# pocket_scope_test_front_end_v0001.net
KiCad netlist of a schematic drawn in EAGLE
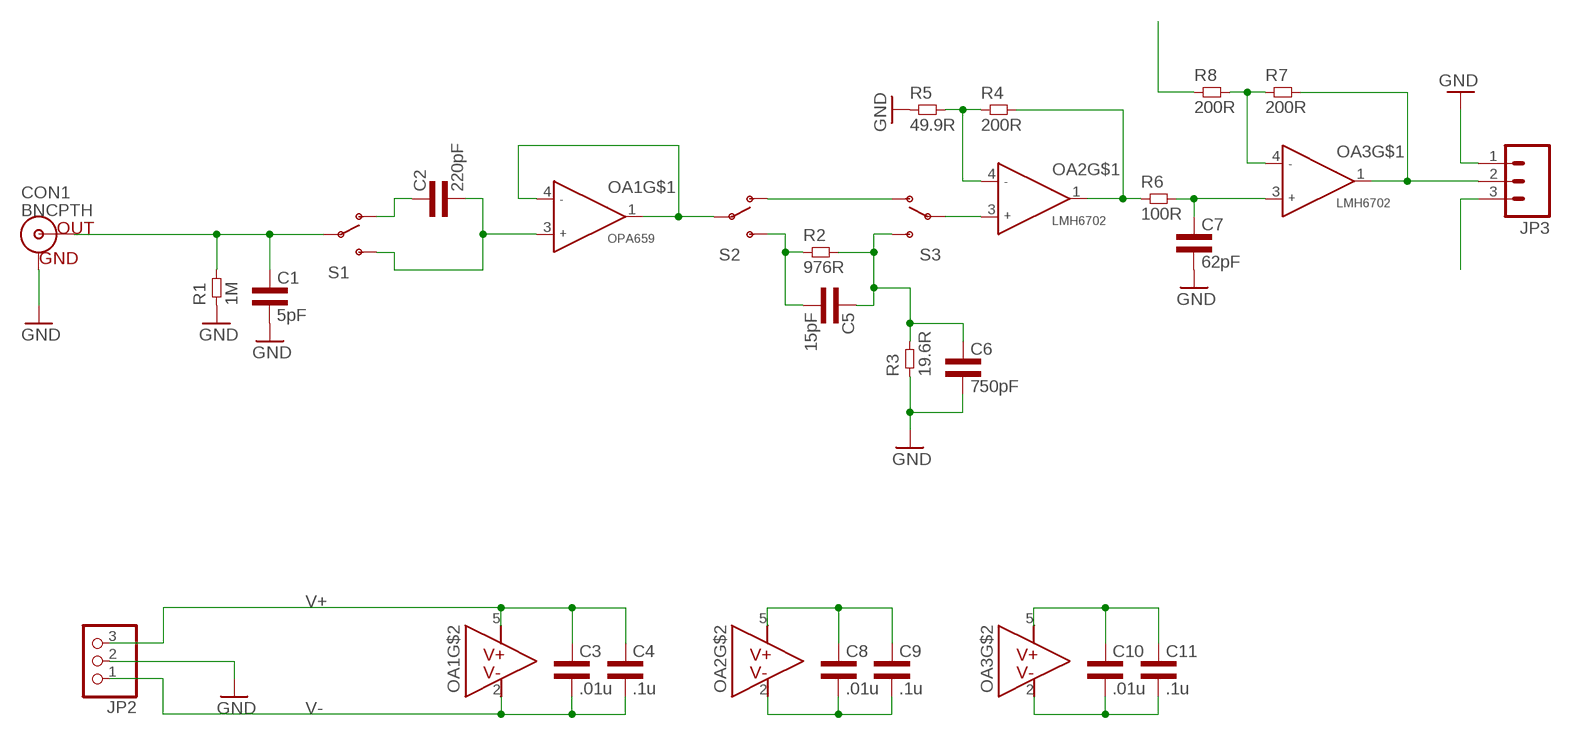
[diagram p0: schematic, sheet 1]

(export (version "E")
  (design (tool "Eeschema 10.0.6"))
  (components
    (comp (ref "C1")
      (value "5pF")
      (footprint "eagle-import:0805L3")
      (libsource (lib "eagle-import") (part "CAP0805L3"))
    )
    (comp (ref "C2")
      (value "220pF")
      (footprint "eagle-import:0805L3")
      (libsource (lib "eagle-import") (part "CAP0805L3"))
    )
    (comp (ref "C3")
      (value ".01u")
      (footprint "eagle-import:0805L3")
      (libsource (lib "eagle-import") (part "CAP0805L3"))
    )
    (comp (ref "C4")
      (value ".1u")
      (footprint "eagle-import:0805L3")
      (libsource (lib "eagle-import") (part "CAP0805L3"))
    )
    (comp (ref "C5")
      (value "15pF")
      (footprint "eagle-import:0805L3")
      (libsource (lib "eagle-import") (part "CAP0805L3"))
    )
    (comp (ref "C6")
      (value "750pF")
      (footprint "eagle-import:0805L3")
      (libsource (lib "eagle-import") (part "CAP0805L3"))
    )
    (comp (ref "C7")
      (value "62pF")
      (footprint "eagle-import:0805L3")
      (libsource (lib "eagle-import") (part "CAP0805L3"))
    )
    (comp (ref "C8")
      (value ".01u")
      (footprint "eagle-import:0805L3")
      (libsource (lib "eagle-import") (part "CAP0805L3"))
    )
    (comp (ref "C9")
      (value ".1u")
      (footprint "eagle-import:0805L3")
      (libsource (lib "eagle-import") (part "CAP0805L3"))
    )
    (comp (ref "C10")
      (value ".01u")
      (footprint "eagle-import:0805L3")
      (libsource (lib "eagle-import") (part "CAP0805L3"))
    )
    (comp (ref "C11")
      (value ".1u")
      (footprint "eagle-import:0805L3")
      (libsource (lib "eagle-import") (part "CAP0805L3"))
    )
    (comp (ref "CON1")
      (value "BNCPTH")
      (footprint "eagle-import:BNC")
      (libsource (lib "eagle-import") (part "BNCPTH"))
    )
    (comp (ref "JP2")
      (value "PINHD-1X3")
      (footprint "eagle-import:1X03")
      (libsource (lib "eagle-import") (part "PINHD-1X3"))
    )
    (comp (ref "JP3")
      (value "M03LOCK")
      (footprint "eagle-import:1X03_LOCK")
      (libsource (lib "eagle-import") (part "M03LOCK"))
    )
    (comp (ref "OA1")
      (value "OPA659")
      (footprint "eagle-import:R-PDSO-G5")
      (libsource (lib "eagle-import") (part "OPA659DBV"))
    )
    (comp (ref "OA2")
      (value "LMH6702")
      (footprint "eagle-import:R-PDSO-G5")
      (libsource (lib "eagle-import") (part "OPA659DBV"))
    )
    (comp (ref "OA3")
      (value "LMH6702")
      (footprint "eagle-import:R-PDSO-G5")
      (libsource (lib "eagle-import") (part "OPA659DBV"))
    )
    (comp (ref "R1")
      (value "1M")
      (footprint "eagle-import:0805L3")
      (libsource (lib "eagle-import") (part "RES0805L3"))
    )
    (comp (ref "R2")
      (value "976R")
      (footprint "eagle-import:0805L3")
      (libsource (lib "eagle-import") (part "RES0805L3"))
    )
    (comp (ref "R3")
      (value "19.6R")
      (footprint "eagle-import:0805L3")
      (libsource (lib "eagle-import") (part "RES0805L3"))
    )
    (comp (ref "R4")
      (value "200R")
      (footprint "eagle-import:0805L3")
      (libsource (lib "eagle-import") (part "RES0805L3"))
    )
    (comp (ref "R5")
      (value "49.9R")
      (footprint "eagle-import:0805L3")
      (libsource (lib "eagle-import") (part "RES0805L3"))
    )
    (comp (ref "R6")
      (value "100R")
      (footprint "eagle-import:0805L3")
      (libsource (lib "eagle-import") (part "RES0805L3"))
    )
    (comp (ref "R7")
      (value "200R")
      (footprint "eagle-import:0805L3")
      (libsource (lib "eagle-import") (part "RES0805L3"))
    )
    (comp (ref "R8")
      (value "200R")
      (footprint "eagle-import:0805L3")
      (libsource (lib "eagle-import") (part "RES0805L3"))
    )
    (comp (ref "S1")
      (value "SPARKFUN-ELECTROMECHANICAL_SWITCH-SPDTPTH_LOCK")
      (footprint "eagle-import:SPARKFUN-ELECTROMECHANICAL_SWITCH-SPDT_LOCK.007S")
      (libsource (lib "eagle-import") (part "SPARKFUN-ELECTROMECHANICAL_SWITCH-SPDTPTH_LOCK"))
    )
    (comp (ref "S2")
      (value "SPARKFUN-ELECTROMECHANICAL_SWITCH-SPDTPTH_LOCK")
      (footprint "eagle-import:SPARKFUN-ELECTROMECHANICAL_SWITCH-SPDT_LOCK.007S")
      (libsource (lib "eagle-import") (part "SPARKFUN-ELECTROMECHANICAL_SWITCH-SPDTPTH_LOCK"))
    )
    (comp (ref "S3")
      (value "SPARKFUN-ELECTROMECHANICAL_SWITCH-SPDTPTH_LOCK")
      (footprint "eagle-import:SPARKFUN-ELECTROMECHANICAL_SWITCH-SPDT_LOCK.007S")
      (libsource (lib "eagle-import") (part "SPARKFUN-ELECTROMECHANICAL_SWITCH-SPDTPTH_LOCK"))
    )
  )
  (nets
    (net (code "1") (name "/V+") (class "Default")
      (node (ref "C10") (pin "1") (pinfunction "1_1") (pintype "bidirectional"))
      (node (ref "C11") (pin "1") (pinfunction "1_1") (pintype "bidirectional"))
      (node (ref "C3") (pin "1") (pinfunction "1_1") (pintype "bidirectional"))
      (node (ref "C4") (pin "1") (pinfunction "1_1") (pintype "bidirectional"))
      (node (ref "C8") (pin "1") (pinfunction "1_1") (pintype "bidirectional"))
      (node (ref "C9") (pin "1") (pinfunction "1_1") (pintype "bidirectional"))
      (node (ref "JP2") (pin "3") (pinfunction "3_3") (pintype "passive"))
      (node (ref "OA1") (pin "5") (pinfunction "V+_5") (pintype "power_in"))
      (node (ref "OA2") (pin "5") (pinfunction "V+_5") (pintype "power_in"))
      (node (ref "OA3") (pin "5") (pinfunction "V+_5") (pintype "power_in"))
    )
    (net (code "2") (name "/V-") (class "Default")
      (node (ref "C10") (pin "2") (pinfunction "2_2") (pintype "bidirectional"))
      (node (ref "C11") (pin "2") (pinfunction "2_2") (pintype "bidirectional"))
      (node (ref "C3") (pin "2") (pinfunction "2_2") (pintype "bidirectional"))
      (node (ref "C4") (pin "2") (pinfunction "2_2") (pintype "bidirectional"))
      (node (ref "C8") (pin "2") (pinfunction "2_2") (pintype "bidirectional"))
      (node (ref "C9") (pin "2") (pinfunction "2_2") (pintype "bidirectional"))
      (node (ref "JP2") (pin "1") (pinfunction "1_1") (pintype "passive"))
      (node (ref "OA1") (pin "2") (pinfunction "V-_2") (pintype "power_in"))
      (node (ref "OA2") (pin "2") (pinfunction "V-_2") (pintype "power_in"))
      (node (ref "OA3") (pin "2") (pinfunction "V-_2") (pintype "power_in"))
    )
    (net (code "3") (name "/V_OS") (class "Default")
      (node (ref "JP3") (pin "3") (pinfunction "3_3") (pintype "passive"))
      (node (ref "R8") (pin "1") (pinfunction "1_1") (pintype "bidirectional"))
    )
    (net (code "4") (name "GND") (class "Default")
      (node (ref "C1") (pin "2") (pinfunction "2_2") (pintype "bidirectional"))
      (node (ref "C6") (pin "2") (pinfunction "2_2") (pintype "bidirectional"))
      (node (ref "C7") (pin "2") (pinfunction "2_2") (pintype "bidirectional"))
      (node (ref "CON1") (pin "GND") (pinfunction "GND_GND") (pintype "bidirectional"))
      (node (ref "JP2") (pin "2") (pinfunction "2_2") (pintype "passive"))
      (node (ref "JP3") (pin "1") (pinfunction "1_1") (pintype "passive"))
      (node (ref "R1") (pin "1") (pinfunction "1_1") (pintype "bidirectional"))
      (node (ref "R3") (pin "1") (pinfunction "1_1") (pintype "bidirectional"))
      (node (ref "R5") (pin "1") (pinfunction "1_1") (pintype "bidirectional"))
    )
    (net (code "5") (name "Net-(CON1-OUT)") (class "Default")
      (node (ref "C1") (pin "1") (pinfunction "1_1") (pintype "bidirectional"))
      (node (ref "CON1") (pin "S") (pinfunction "OUT_S") (pintype "bidirectional"))
      (node (ref "R1") (pin "2") (pinfunction "2_2") (pintype "bidirectional"))
      (node (ref "S1") (pin "2") (pinfunction "P_2") (pintype "passive"))
    )
    (net (code "6") (name "Net-(OA1A-INA+)") (class "Default")
      (node (ref "C2") (pin "2") (pinfunction "2_2") (pintype "bidirectional"))
      (node (ref "OA1") (pin "3") (pinfunction "INA+_3") (pintype "bidirectional"))
      (node (ref "S1") (pin "3") (pinfunction "S_3") (pintype "passive"))
    )
    (net (code "7") (name "Net-(OA1A-INA-)") (class "Default")
      (node (ref "OA1") (pin "1") (pinfunction "OUTA_1") (pintype "bidirectional"))
      (node (ref "OA1") (pin "4") (pinfunction "INA-_4") (pintype "bidirectional"))
      (node (ref "S2") (pin "2") (pinfunction "P_2") (pintype "passive"))
    )
    (net (code "8") (name "Net-(OA2A-INA+)") (class "Default")
      (node (ref "OA2") (pin "3") (pinfunction "INA+_3") (pintype "bidirectional"))
      (node (ref "S3") (pin "2") (pinfunction "P_2") (pintype "passive"))
    )
    (net (code "9") (name "Net-(OA2A-INA-)") (class "Default")
      (node (ref "OA2") (pin "4") (pinfunction "INA-_4") (pintype "bidirectional"))
      (node (ref "R4") (pin "1") (pinfunction "1_1") (pintype "bidirectional"))
      (node (ref "R5") (pin "2") (pinfunction "2_2") (pintype "bidirectional"))
    )
    (net (code "10") (name "Net-(OA2A-OUTA)") (class "Default")
      (node (ref "OA2") (pin "1") (pinfunction "OUTA_1") (pintype "bidirectional"))
      (node (ref "R4") (pin "2") (pinfunction "2_2") (pintype "bidirectional"))
      (node (ref "R6") (pin "1") (pinfunction "1_1") (pintype "bidirectional"))
    )
    (net (code "11") (name "Net-(OA3A-INA+)") (class "Default")
      (node (ref "C7") (pin "1") (pinfunction "1_1") (pintype "bidirectional"))
      (node (ref "OA3") (pin "3") (pinfunction "INA+_3") (pintype "bidirectional"))
      (node (ref "R6") (pin "2") (pinfunction "2_2") (pintype "bidirectional"))
    )
    (net (code "12") (name "Net-(OA3A-INA-)") (class "Default")
      (node (ref "OA3") (pin "4") (pinfunction "INA-_4") (pintype "bidirectional"))
      (node (ref "R7") (pin "1") (pinfunction "1_1") (pintype "bidirectional"))
      (node (ref "R8") (pin "2") (pinfunction "2_2") (pintype "bidirectional"))
    )
    (net (code "13") (name "Net-(OA3A-OUTA)") (class "Default")
      (node (ref "JP3") (pin "2") (pinfunction "2_2") (pintype "passive"))
      (node (ref "OA3") (pin "1") (pinfunction "OUTA_1") (pintype "bidirectional"))
      (node (ref "R7") (pin "2") (pinfunction "2_2") (pintype "bidirectional"))
    )
    (net (code "14") (name "Net-(S1-O)") (class "Default")
      (node (ref "C2") (pin "1") (pinfunction "1_1") (pintype "bidirectional"))
      (node (ref "S1") (pin "1") (pinfunction "O_1") (pintype "passive"))
    )
    (net (code "15") (name "Net-(S2-O)") (class "Default")
      (node (ref "S2") (pin "1") (pinfunction "O_1") (pintype "passive"))
      (node (ref "S3") (pin "1") (pinfunction "O_1") (pintype "passive"))
    )
    (net (code "16") (name "Net-(S2-S)") (class "Default")
      (node (ref "C5") (pin "2") (pinfunction "2_2") (pintype "bidirectional"))
      (node (ref "R2") (pin "1") (pinfunction "1_1") (pintype "bidirectional"))
      (node (ref "S2") (pin "3") (pinfunction "S_3") (pintype "passive"))
    )
    (net (code "17") (name "Net-(S3-S)") (class "Default")
      (node (ref "C5") (pin "1") (pinfunction "1_1") (pintype "bidirectional"))
      (node (ref "C6") (pin "1") (pinfunction "1_1") (pintype "bidirectional"))
      (node (ref "R2") (pin "2") (pinfunction "2_2") (pintype "bidirectional"))
      (node (ref "R3") (pin "2") (pinfunction "2_2") (pintype "bidirectional"))
      (node (ref "S3") (pin "3") (pinfunction "S_3") (pintype "passive"))
    )
  )
)
